# Vertap_MCU.net
KiCad netlist of a schematic drawn in Altium Designer
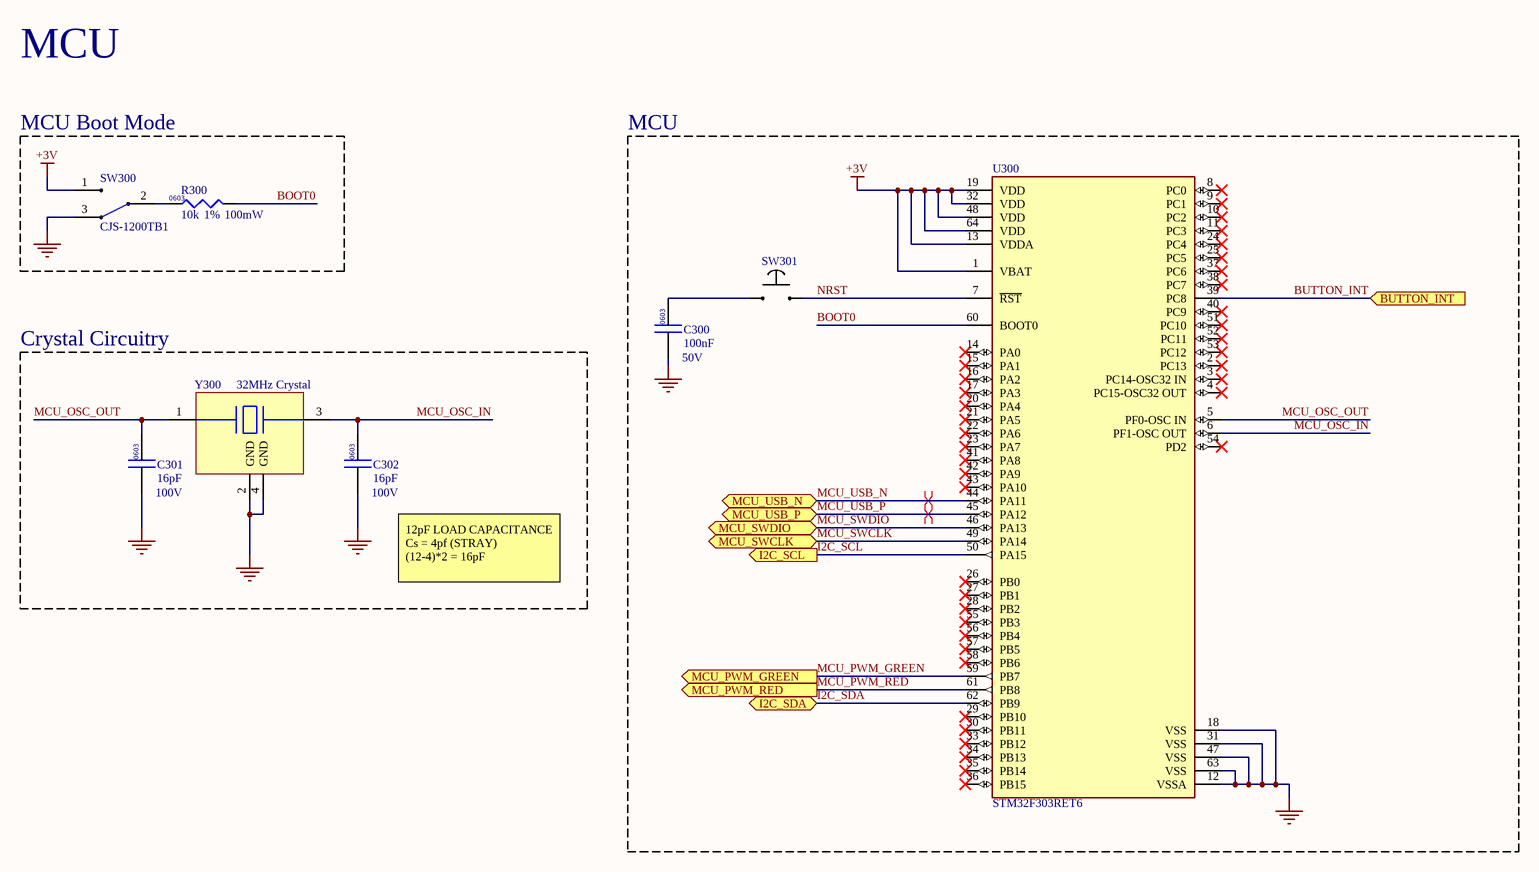
[diagram p0: Vertap_MCU.SchDoc]

(export (version "E")
  (design (tool "Eeschema 10.0.6"))
  (components
    (comp (ref "C300")
      (value "100nF")
      (footprint "CAP_0603_MURATA")
      (description "CAP CER 0.1UF 50V X7R 0603")
      (libsource (lib "Vertap_SchLib") (part "CAP_0.1uF_0603"))
    )
    (comp (ref "C301")
      (value "16pF")
      (footprint "CAP_0603_MURATA")
      (description "CAP CER 16PF 100V C0G/NP0 0603")
      (libsource (lib "Vertap_SchLib") (part "CAP_16pF_0603"))
    )
    (comp (ref "C302")
      (value "16pF")
      (footprint "CAP_0603_MURATA")
      (description "CAP CER 16PF 100V C0G/NP0 0603")
      (libsource (lib "Vertap_SchLib") (part "CAP_16pF_0603"))
    )
    (comp (ref "R300")
      (value "10k")
      (footprint "RES_0603_YAGEO")
      (description "RES 10K OHM 1% 1/10W 0603")
      (fields
        (field (name "MANUFACTURER") "YAGEO")
        (field (name "MANUFACTURER PART NUMBER") "AC0603FR-1310KL")
      )
      (libsource (lib "Vertap_SchLib") (part "RES_0603_10K"))
    )
    (comp (ref "SW300")
      (value "CJS-1200TB1")
      (footprint "CJS-1200TB1")
      (description "SWITCH SLIDE SPDT 100MA 6V")
      (libsource (lib "Vertap_SchLib") (part "CJS-1200TB1"))
    )
    (comp (ref "SW301")
      (value "LS38G2F-T")
      (footprint "LS38G2F-T")
      (description "TOP-PRESS TACTILE SWITCH")
      (libsource (lib "Vertap_SchLib") (part "LS38G2F-T"))
    )
    (comp (ref "U300")
      (value "STM32F303RET6")
      (footprint "FP-LQFP64-5W-MFG")
      (description "IC MCU 32BIT 512KB FLASH 64LQFP")
      (fields
        (field (name "MANUFACTURER") "STMicroelectronics")
        (field (name "OCTOPART") "https://octopart.com/stm32f303ret6-stmicroelectronics-53115257")
      )
      (libsource (lib "Altium Content Vault") (part "7a78af9fccac3dafce8a4966595e415"))
    )
    (comp (ref "Y300")
      (value "32MHz Crystal")
      (footprint "CX2016SA32000H0FLJG1")
      (description "32 MHz ±10ppm Crystal 12pF 60 Ohms 4-SMD, No Lead")
      (libsource (lib "Vertap_SchLib") (part "CX2016SA32000H0FLJG1"))
    )
  )
  (nets
    (net (code "1") (name "+3V") (class "Default")
      (node (ref "SW300") (pin "1") (pinfunction "1_1") (pintype "passive"))
      (node (ref "U300") (pin "1") (pinfunction "VBAT_1") (pintype "power_in"))
      (node (ref "U300") (pin "13") (pinfunction "VDDA_13") (pintype "power_in"))
      (node (ref "U300") (pin "19") (pinfunction "VDD_19") (pintype "power_in"))
      (node (ref "U300") (pin "32") (pinfunction "VDD_32") (pintype "power_in"))
      (node (ref "U300") (pin "48") (pinfunction "VDD_48") (pintype "power_in"))
      (node (ref "U300") (pin "64") (pinfunction "VDD_64") (pintype "power_in"))
    )
    (net (code "2") (name "/BOOT0") (class "Default")
      (node (ref "R300") (pin "2") (pinfunction "2_2") (pintype "passive"))
      (node (ref "U300") (pin "60") (pinfunction "BOOT0_60") (pintype "passive"))
    )
    (net (code "3") (name "/BUTTON_INT") (class "Default")
      (node (ref "U300") (pin "39") (pinfunction "PC8_39") (pintype "passive"))
    )
    (net (code "4") (name "/I2C_SCL") (class "Default")
      (node (ref "U300") (pin "50") (pinfunction "PA15_50") (pintype "output"))
    )
    (net (code "5") (name "/I2C_SDA") (class "Default")
      (node (ref "U300") (pin "62") (pinfunction "PB9_62") (pintype "bidirectional"))
    )
    (net (code "6") (name "/MCU_OSC_IN") (class "Default")
      (node (ref "C302") (pin "1") (pinfunction "1_1") (pintype "passive"))
      (node (ref "U300") (pin "6") (pinfunction "PF1-OSC_OUT_6") (pintype "bidirectional"))
      (node (ref "Y300") (pin "3") (pinfunction "OUT_3") (pintype "passive"))
    )
    (net (code "7") (name "/MCU_OSC_OUT") (class "Default")
      (node (ref "C301") (pin "1") (pinfunction "1_1") (pintype "passive"))
      (node (ref "U300") (pin "5") (pinfunction "PF0-OSC_IN_5") (pintype "bidirectional"))
      (node (ref "Y300") (pin "1") (pinfunction "IN_1") (pintype "passive"))
    )
    (net (code "8") (name "/MCU_PWM_GREEN") (class "Default")
      (node (ref "U300") (pin "59") (pinfunction "PB7_59") (pintype "output"))
    )
    (net (code "9") (name "/MCU_PWM_RED") (class "Default")
      (node (ref "U300") (pin "61") (pinfunction "PB8_61") (pintype "output"))
    )
    (net (code "10") (name "/MCU_SWCLK") (class "Default")
      (node (ref "U300") (pin "49") (pinfunction "PA14_49") (pintype "bidirectional"))
    )
    (net (code "11") (name "/MCU_SWDIO") (class "Default")
      (node (ref "U300") (pin "46") (pinfunction "PA13_46") (pintype "bidirectional"))
    )
    (net (code "12") (name "/MCU_USB_N") (class "Default")
      (node (ref "U300") (pin "44") (pinfunction "PA11_44") (pintype "bidirectional"))
    )
    (net (code "13") (name "/MCU_USB_P") (class "Default")
      (node (ref "U300") (pin "45") (pinfunction "PA12_45") (pintype "bidirectional"))
    )
    (net (code "14") (name "/NRST") (class "Default")
      (node (ref "SW301") (pin "2") (pinfunction "1_2") (pintype "passive"))
      (node (ref "U300") (pin "7") (pinfunction "~{RST}_7") (pintype "passive"))
    )
    (net (code "15") (name "GND") (class "Default")
      (node (ref "C300") (pin "2") (pinfunction "2_2") (pintype "passive"))
      (node (ref "C301") (pin "2") (pinfunction "2_2") (pintype "passive"))
      (node (ref "C302") (pin "2") (pinfunction "2_2") (pintype "passive"))
      (node (ref "SW300") (pin "3") (pinfunction "3_3") (pintype "passive"))
      (node (ref "U300") (pin "12") (pinfunction "VSSA_12") (pintype "power_in"))
      (node (ref "U300") (pin "18") (pinfunction "VSS_18") (pintype "power_in"))
      (node (ref "U300") (pin "31") (pinfunction "VSS_31") (pintype "power_in"))
      (node (ref "U300") (pin "47") (pinfunction "VSS_47") (pintype "power_in"))
      (node (ref "U300") (pin "63") (pinfunction "VSS_63") (pintype "power_in"))
      (node (ref "Y300") (pin "2") (pinfunction "GND_2") (pintype "passive"))
      (node (ref "Y300") (pin "4") (pinfunction "GND_4") (pintype "passive"))
    )
    (net (code "16") (name "Net-(R300-Pad1)") (class "Default")
      (node (ref "R300") (pin "1") (pinfunction "1_1") (pintype "passive"))
      (node (ref "SW300") (pin "2") (pinfunction "2_2") (pintype "passive"))
    )
    (net (code "17") (name "Net-(SW301-0)") (class "Default")
      (node (ref "C300") (pin "1") (pinfunction "1_1") (pintype "passive"))
      (node (ref "SW301") (pin "1") (pinfunction "0_1") (pintype "passive"))
    )
    (net (code "18") (name "unconnected-(U300-PA0-Pad14)") (class "Default")
      (node (ref "U300") (pin "14") (pinfunction "PA0_14") (pintype "bidirectional+no_connect"))
    )
    (net (code "19") (name "unconnected-(U300-PA1-Pad15)") (class "Default")
      (node (ref "U300") (pin "15") (pinfunction "PA1_15") (pintype "bidirectional+no_connect"))
    )
    (net (code "20") (name "unconnected-(U300-PA2-Pad16)") (class "Default")
      (node (ref "U300") (pin "16") (pinfunction "PA2_16") (pintype "bidirectional+no_connect"))
    )
    (net (code "21") (name "unconnected-(U300-PA3-Pad17)") (class "Default")
      (node (ref "U300") (pin "17") (pinfunction "PA3_17") (pintype "bidirectional+no_connect"))
    )
    (net (code "22") (name "unconnected-(U300-PA4-Pad20)") (class "Default")
      (node (ref "U300") (pin "20") (pinfunction "PA4_20") (pintype "bidirectional+no_connect"))
    )
    (net (code "23") (name "unconnected-(U300-PA5-Pad21)") (class "Default")
      (node (ref "U300") (pin "21") (pinfunction "PA5_21") (pintype "bidirectional+no_connect"))
    )
    (net (code "24") (name "unconnected-(U300-PA6-Pad22)") (class "Default")
      (node (ref "U300") (pin "22") (pinfunction "PA6_22") (pintype "bidirectional+no_connect"))
    )
    (net (code "25") (name "unconnected-(U300-PA7-Pad23)") (class "Default")
      (node (ref "U300") (pin "23") (pinfunction "PA7_23") (pintype "bidirectional+no_connect"))
    )
    (net (code "26") (name "unconnected-(U300-PA8-Pad41)") (class "Default")
      (node (ref "U300") (pin "41") (pinfunction "PA8_41") (pintype "bidirectional+no_connect"))
    )
    (net (code "27") (name "unconnected-(U300-PA9-Pad42)") (class "Default")
      (node (ref "U300") (pin "42") (pinfunction "PA9_42") (pintype "bidirectional+no_connect"))
    )
    (net (code "28") (name "unconnected-(U300-PA10-Pad43)") (class "Default")
      (node (ref "U300") (pin "43") (pinfunction "PA10_43") (pintype "bidirectional+no_connect"))
    )
    (net (code "29") (name "unconnected-(U300-PB0-Pad26)") (class "Default")
      (node (ref "U300") (pin "26") (pinfunction "PB0_26") (pintype "bidirectional+no_connect"))
    )
    (net (code "30") (name "unconnected-(U300-PB1-Pad27)") (class "Default")
      (node (ref "U300") (pin "27") (pinfunction "PB1_27") (pintype "bidirectional+no_connect"))
    )
    (net (code "31") (name "unconnected-(U300-PB2-Pad28)") (class "Default")
      (node (ref "U300") (pin "28") (pinfunction "PB2_28") (pintype "bidirectional+no_connect"))
    )
    (net (code "32") (name "unconnected-(U300-PB3-Pad55)") (class "Default")
      (node (ref "U300") (pin "55") (pinfunction "PB3_55") (pintype "bidirectional+no_connect"))
    )
    (net (code "33") (name "unconnected-(U300-PB4-Pad56)") (class "Default")
      (node (ref "U300") (pin "56") (pinfunction "PB4_56") (pintype "bidirectional+no_connect"))
    )
    (net (code "34") (name "unconnected-(U300-PB5-Pad57)") (class "Default")
      (node (ref "U300") (pin "57") (pinfunction "PB5_57") (pintype "bidirectional+no_connect"))
    )
    (net (code "35") (name "unconnected-(U300-PB6-Pad58)") (class "Default")
      (node (ref "U300") (pin "58") (pinfunction "PB6_58") (pintype "bidirectional+no_connect"))
    )
    (net (code "36") (name "unconnected-(U300-PB10-Pad29)") (class "Default")
      (node (ref "U300") (pin "29") (pinfunction "PB10_29") (pintype "bidirectional+no_connect"))
    )
    (net (code "37") (name "unconnected-(U300-PB11-Pad30)") (class "Default")
      (node (ref "U300") (pin "30") (pinfunction "PB11_30") (pintype "bidirectional+no_connect"))
    )
    (net (code "38") (name "unconnected-(U300-PB12-Pad33)") (class "Default")
      (node (ref "U300") (pin "33") (pinfunction "PB12_33") (pintype "bidirectional+no_connect"))
    )
    (net (code "39") (name "unconnected-(U300-PB13-Pad34)") (class "Default")
      (node (ref "U300") (pin "34") (pinfunction "PB13_34") (pintype "bidirectional+no_connect"))
    )
    (net (code "40") (name "unconnected-(U300-PB14-Pad35)") (class "Default")
      (node (ref "U300") (pin "35") (pinfunction "PB14_35") (pintype "bidirectional+no_connect"))
    )
    (net (code "41") (name "unconnected-(U300-PB15-Pad36)") (class "Default")
      (node (ref "U300") (pin "36") (pinfunction "PB15_36") (pintype "bidirectional+no_connect"))
    )
    (net (code "42") (name "unconnected-(U300-PC0-Pad8)") (class "Default")
      (node (ref "U300") (pin "8") (pinfunction "PC0_8") (pintype "bidirectional+no_connect"))
    )
    (net (code "43") (name "unconnected-(U300-PC1-Pad9)") (class "Default")
      (node (ref "U300") (pin "9") (pinfunction "PC1_9") (pintype "bidirectional+no_connect"))
    )
    (net (code "44") (name "unconnected-(U300-PC2-Pad10)") (class "Default")
      (node (ref "U300") (pin "10") (pinfunction "PC2_10") (pintype "bidirectional+no_connect"))
    )
    (net (code "45") (name "unconnected-(U300-PC3-Pad11)") (class "Default")
      (node (ref "U300") (pin "11") (pinfunction "PC3_11") (pintype "bidirectional+no_connect"))
    )
    (net (code "46") (name "unconnected-(U300-PC4-Pad24)") (class "Default")
      (node (ref "U300") (pin "24") (pinfunction "PC4_24") (pintype "bidirectional+no_connect"))
    )
    (net (code "47") (name "unconnected-(U300-PC5-Pad25)") (class "Default")
      (node (ref "U300") (pin "25") (pinfunction "PC5_25") (pintype "bidirectional+no_connect"))
    )
    (net (code "48") (name "unconnected-(U300-PC6-Pad37)") (class "Default")
      (node (ref "U300") (pin "37") (pinfunction "PC6_37") (pintype "bidirectional+no_connect"))
    )
    (net (code "49") (name "unconnected-(U300-PC7-Pad38)") (class "Default")
      (node (ref "U300") (pin "38") (pinfunction "PC7_38") (pintype "bidirectional+no_connect"))
    )
    (net (code "50") (name "unconnected-(U300-PC9-Pad40)") (class "Default")
      (node (ref "U300") (pin "40") (pinfunction "PC9_40") (pintype "bidirectional+no_connect"))
    )
    (net (code "51") (name "unconnected-(U300-PC10-Pad51)") (class "Default")
      (node (ref "U300") (pin "51") (pinfunction "PC10_51") (pintype "bidirectional+no_connect"))
    )
    (net (code "52") (name "unconnected-(U300-PC11-Pad52)") (class "Default")
      (node (ref "U300") (pin "52") (pinfunction "PC11_52") (pintype "bidirectional+no_connect"))
    )
    (net (code "53") (name "unconnected-(U300-PC12-Pad53)") (class "Default")
      (node (ref "U300") (pin "53") (pinfunction "PC12_53") (pintype "bidirectional+no_connect"))
    )
    (net (code "54") (name "unconnected-(U300-PC13-Pad2)") (class "Default")
      (node (ref "U300") (pin "2") (pinfunction "PC13_2") (pintype "bidirectional+no_connect"))
    )
    (net (code "55") (name "unconnected-(U300-PC14-OSC32_IN-Pad3)") (class "Default")
      (node (ref "U300") (pin "3") (pinfunction "PC14-OSC32_IN_3") (pintype "bidirectional+no_connect"))
    )
    (net (code "56") (name "unconnected-(U300-PC15-OSC32_OUT-Pad4)") (class "Default")
      (node (ref "U300") (pin "4") (pinfunction "PC15-OSC32_OUT_4") (pintype "bidirectional+no_connect"))
    )
    (net (code "57") (name "unconnected-(U300-PD2-Pad54)") (class "Default")
      (node (ref "U300") (pin "54") (pinfunction "PD2_54") (pintype "bidirectional+no_connect"))
    )
  )
)
